# VR_78XX_1.net
KiCad netlist of a schematic drawn in EAGLE
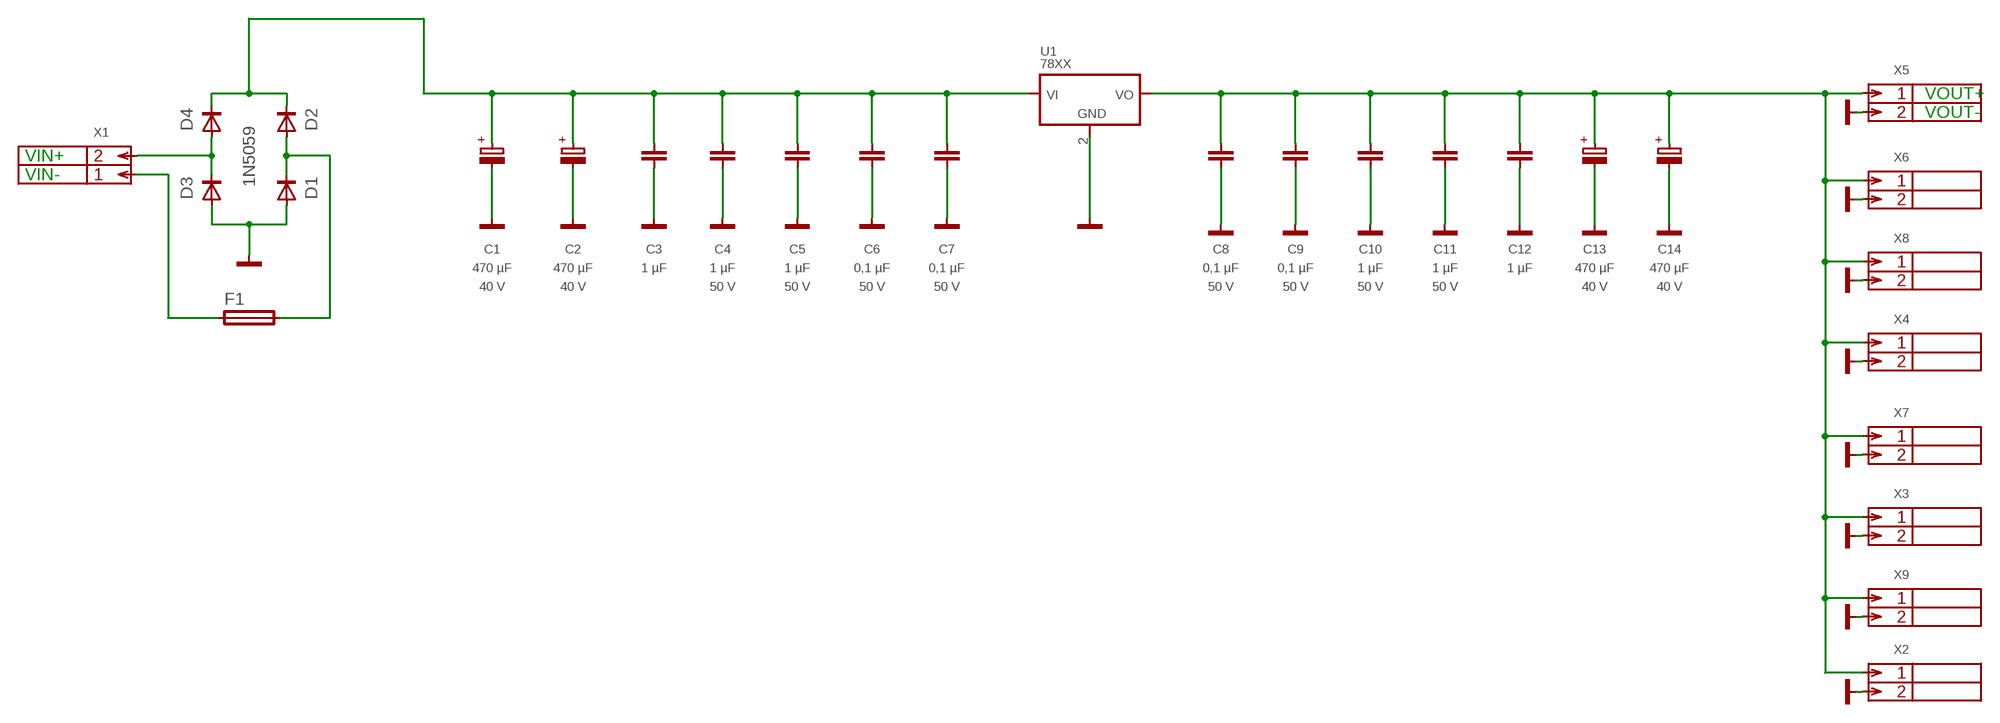
[diagram p0: schematic, sheet 1]

(export (version "E")
  (design (tool "Eeschema 10.0.6"))
  (components
    (comp (ref "C1")
      (value "470 µF")
      (footprint "eagle-import:AHT10-30C")
      (fields (field (name "VOLTAGE") "100 V") (field (name "VOLTAGE_1") "40 V"))
      (libsource (lib "eagle-import") (part "BEYSHLAG-118/119AHTC"))
    )
    (comp (ref "C2")
      (value "470 µF")
      (footprint "eagle-import:AHT10-30C")
      (fields (field (name "VOLTAGE") "100 V") (field (name "VOLTAGE_1") "40 V"))
      (libsource (lib "eagle-import") (part "BEYSHLAG-118/119AHTC"))
    )
    (comp (ref "C3") (value "1 µF") (footprint "eagle-import:1") (libsource (lib "eagle-import") (part "1")))
    (comp (ref "C4")
      (value "1 µF")
      (footprint "eagle-import:C050-025X075")
      (fields (field (name "VOLTAGE") "50 V") (field (name "TOLERANCE") "10 %"))
      (libsource (lib "eagle-import") (part "C-EU050-025X075"))
    )
    (comp (ref "C5")
      (value "1 µF")
      (footprint "eagle-import:C050-025X075")
      (fields (field (name "VOLTAGE") "50 V") (field (name "TOLERANCE") "10 %"))
      (libsource (lib "eagle-import") (part "C-EU050-025X075"))
    )
    (comp (ref "C6")
      (value "0,1 µF")
      (footprint "eagle-import:C050-025X075")
      (fields (field (name "VOLTAGE") "50 V") (field (name "TOLERANCE") "10 %"))
      (libsource (lib "eagle-import") (part "C-EU050-025X075"))
    )
    (comp (ref "C7")
      (value "0,1 µF")
      (footprint "eagle-import:C050-025X075")
      (fields (field (name "VOLTAGE") "50 V") (field (name "TOLERANCE") "10 %"))
      (libsource (lib "eagle-import") (part "C-EU050-025X075"))
    )
    (comp (ref "C8")
      (value "0,1 µF")
      (footprint "eagle-import:C050-025X075")
      (fields (field (name "VOLTAGE") "50 V") (field (name "TOLERANCE") "10 %"))
      (libsource (lib "eagle-import") (part "C-EU050-025X075"))
    )
    (comp (ref "C9")
      (value "0,1 µF")
      (footprint "eagle-import:C050-025X075")
      (fields (field (name "VOLTAGE") "50 V") (field (name "TOLERANCE") "10 %"))
      (libsource (lib "eagle-import") (part "C-EU050-025X075"))
    )
    (comp (ref "C10")
      (value "1 µF")
      (footprint "eagle-import:C050-025X075")
      (fields (field (name "VOLTAGE") "50 V") (field (name "TOLERANCE") "10 %"))
      (libsource (lib "eagle-import") (part "C-EU050-025X075"))
    )
    (comp (ref "C11")
      (value "1 µF")
      (footprint "eagle-import:C050-025X075")
      (fields (field (name "VOLTAGE") "50 V") (field (name "TOLERANCE") "10 %"))
      (libsource (lib "eagle-import") (part "C-EU050-025X075"))
    )
    (comp (ref "C12") (value "1 µF") (footprint "eagle-import:1") (libsource (lib "eagle-import") (part "1")))
    (comp (ref "C13")
      (value "470 µF")
      (footprint "eagle-import:AHT10-30C")
      (fields (field (name "VOLTAGE") "100 V") (field (name "VOLTAGE_1") "40 V"))
      (libsource (lib "eagle-import") (part "BEYSHLAG-118/119AHTC"))
    )
    (comp (ref "C14")
      (value "470 µF")
      (footprint "eagle-import:AHT10-30C")
      (fields (field (name "VOLTAGE") "100 V") (field (name "VOLTAGE_1") "40 V"))
      (libsource (lib "eagle-import") (part "BEYSHLAG-118/119AHTC"))
    )
    (comp (ref "D1")
      (value "1N5059")
      (footprint "eagle-import:DO204-10")
      (libsource (lib "eagle-import") (part "1N5059"))
    )
    (comp (ref "D2")
      (value "1N5059")
      (footprint "eagle-import:DO204-10")
      (libsource (lib "eagle-import") (part "1N5059"))
    )
    (comp (ref "D3")
      (value "1N5059")
      (footprint "eagle-import:DO204-10")
      (libsource (lib "eagle-import") (part "1N5059"))
    )
    (comp (ref "D4")
      (value "1N5059")
      (footprint "eagle-import:DO204-10")
      (libsource (lib "eagle-import") (part "1N5059"))
    )
    (comp (ref "F1")
      (value "GSH15")
      (footprint "eagle-import:GSH15")
      (libsource (lib "eagle-import") (part "GSH15"))
    )
    (comp (ref "U1")
      (value "78XX")
      (footprint "eagle-import:TO220H")
      (libsource (lib "eagle-import") (part "78T05"))
    )
    (comp (ref "X1")
      (value "AK100V5")
      (footprint "eagle-import:AK100-2V")
      (libsource (lib "eagle-import") (part "AK100V5"))
    )
    (comp (ref "X2")
      (value "MTA02-100")
      (footprint "eagle-import:10X02MTA")
      (libsource (lib "eagle-import") (part "MTA02-100"))
    )
    (comp (ref "X3")
      (value "MTA02-100")
      (footprint "eagle-import:10X02MTA")
      (libsource (lib "eagle-import") (part "MTA02-100"))
    )
    (comp (ref "X4")
      (value "MTA02-100")
      (footprint "eagle-import:10X02MTA")
      (libsource (lib "eagle-import") (part "MTA02-100"))
    )
    (comp (ref "X5")
      (value "MTA02-100")
      (footprint "eagle-import:10X02MTA")
      (libsource (lib "eagle-import") (part "MTA02-100"))
    )
    (comp (ref "X6")
      (value "MTA02-100")
      (footprint "eagle-import:10X02MTA")
      (libsource (lib "eagle-import") (part "MTA02-100"))
    )
    (comp (ref "X7")
      (value "MTA02-100")
      (footprint "eagle-import:10X02MTA")
      (libsource (lib "eagle-import") (part "MTA02-100"))
    )
    (comp (ref "X8")
      (value "MTA02-100")
      (footprint "eagle-import:10X02MTA")
      (libsource (lib "eagle-import") (part "MTA02-100"))
    )
    (comp (ref "X9")
      (value "MTA02-100")
      (footprint "eagle-import:10X02MTA")
      (libsource (lib "eagle-import") (part "MTA02-100"))
    )
  )
  (nets
    (net (code "1") (name "GND") (class "Default")
      (node (ref "C1") (pin "-") (pinfunction "-_-") (pintype "passive"))
      (node (ref "C10") (pin "2") (pinfunction "2_2") (pintype "passive"))
      (node (ref "C11") (pin "2") (pinfunction "2_2") (pintype "passive"))
      (node (ref "C12") (pin "2") (pinfunction "2_2") (pintype "passive"))
      (node (ref "C13") (pin "-") (pinfunction "-_-") (pintype "passive"))
      (node (ref "C14") (pin "-") (pinfunction "-_-") (pintype "passive"))
      (node (ref "C2") (pin "-") (pinfunction "-_-") (pintype "passive"))
      (node (ref "C3") (pin "2") (pinfunction "2_2") (pintype "passive"))
      (node (ref "C4") (pin "2") (pinfunction "2_2") (pintype "passive"))
      (node (ref "C5") (pin "2") (pinfunction "2_2") (pintype "passive"))
      (node (ref "C6") (pin "2") (pinfunction "2_2") (pintype "passive"))
      (node (ref "C7") (pin "2") (pinfunction "2_2") (pintype "passive"))
      (node (ref "C8") (pin "2") (pinfunction "2_2") (pintype "passive"))
      (node (ref "C9") (pin "2") (pinfunction "2_2") (pintype "passive"))
      (node (ref "D1") (pin "A") (pinfunction "A_A") (pintype "passive"))
      (node (ref "D3") (pin "A") (pinfunction "A_A") (pintype "passive"))
      (node (ref "U1") (pin "2") (pinfunction "GND_2") (pintype "passive"))
      (node (ref "X2") (pin "2") (pinfunction "2_2") (pintype "passive"))
      (node (ref "X3") (pin "2") (pinfunction "2_2") (pintype "passive"))
      (node (ref "X4") (pin "2") (pinfunction "2_2") (pintype "passive"))
      (node (ref "X5") (pin "2") (pinfunction "2_2") (pintype "passive"))
      (node (ref "X6") (pin "2") (pinfunction "2_2") (pintype "passive"))
      (node (ref "X7") (pin "2") (pinfunction "2_2") (pintype "passive"))
      (node (ref "X8") (pin "2") (pinfunction "2_2") (pintype "passive"))
      (node (ref "X9") (pin "2") (pinfunction "2_2") (pintype "passive"))
    )
    (net (code "2") (name "Net-(D1-PadC)") (class "Default")
      (node (ref "D1") (pin "C") (pinfunction "C_C") (pintype "passive"))
      (node (ref "D2") (pin "A") (pinfunction "A_A") (pintype "passive"))
      (node (ref "F1") (pin "2") (pinfunction "2_2") (pintype "passive"))
    )
    (net (code "3") (name "Net-(U1-VI)") (class "Default")
      (node (ref "C1") (pin "+") (pinfunction "+_+") (pintype "passive"))
      (node (ref "C2") (pin "+") (pinfunction "+_+") (pintype "passive"))
      (node (ref "C3") (pin "1") (pinfunction "1_1") (pintype "passive"))
      (node (ref "C4") (pin "1") (pinfunction "1_1") (pintype "passive"))
      (node (ref "C5") (pin "1") (pinfunction "1_1") (pintype "passive"))
      (node (ref "C6") (pin "1") (pinfunction "1_1") (pintype "passive"))
      (node (ref "C7") (pin "1") (pinfunction "1_1") (pintype "passive"))
      (node (ref "D2") (pin "C") (pinfunction "C_C") (pintype "passive"))
      (node (ref "D4") (pin "C") (pinfunction "C_C") (pintype "passive"))
      (node (ref "U1") (pin "1") (pinfunction "VI_1") (pintype "input"))
    )
    (net (code "4") (name "Net-(U1-VO)") (class "Default")
      (node (ref "C10") (pin "1") (pinfunction "1_1") (pintype "passive"))
      (node (ref "C11") (pin "1") (pinfunction "1_1") (pintype "passive"))
      (node (ref "C12") (pin "1") (pinfunction "1_1") (pintype "passive"))
      (node (ref "C13") (pin "+") (pinfunction "+_+") (pintype "passive"))
      (node (ref "C14") (pin "+") (pinfunction "+_+") (pintype "passive"))
      (node (ref "C8") (pin "1") (pinfunction "1_1") (pintype "passive"))
      (node (ref "C9") (pin "1") (pinfunction "1_1") (pintype "passive"))
      (node (ref "U1") (pin "3") (pinfunction "VO_3") (pintype "passive"))
      (node (ref "X2") (pin "1") (pinfunction "1_1") (pintype "passive"))
      (node (ref "X3") (pin "1") (pinfunction "1_1") (pintype "passive"))
      (node (ref "X4") (pin "1") (pinfunction "1_1") (pintype "passive"))
      (node (ref "X5") (pin "1") (pinfunction "1_1") (pintype "passive"))
      (node (ref "X6") (pin "1") (pinfunction "1_1") (pintype "passive"))
      (node (ref "X7") (pin "1") (pinfunction "1_1") (pintype "passive"))
      (node (ref "X8") (pin "1") (pinfunction "1_1") (pintype "passive"))
      (node (ref "X9") (pin "1") (pinfunction "1_1") (pintype "passive"))
    )
    (net (code "5") (name "Net-(X1-1)") (class "Default")
      (node (ref "F1") (pin "1") (pinfunction "1_1") (pintype "passive"))
      (node (ref "X1") (pin "P$1") (pinfunction "1_P$1") (pintype "passive"))
    )
    (net (code "6") (name "Net-(X1-2)") (class "Default")
      (node (ref "D3") (pin "C") (pinfunction "C_C") (pintype "passive"))
      (node (ref "D4") (pin "A") (pinfunction "A_A") (pintype "passive"))
      (node (ref "X1") (pin "P$2") (pinfunction "2_P$2") (pintype "passive"))
    )
  )
)
